# Photodiode.net
KiCad netlist of a schematic drawn in Altium Designer
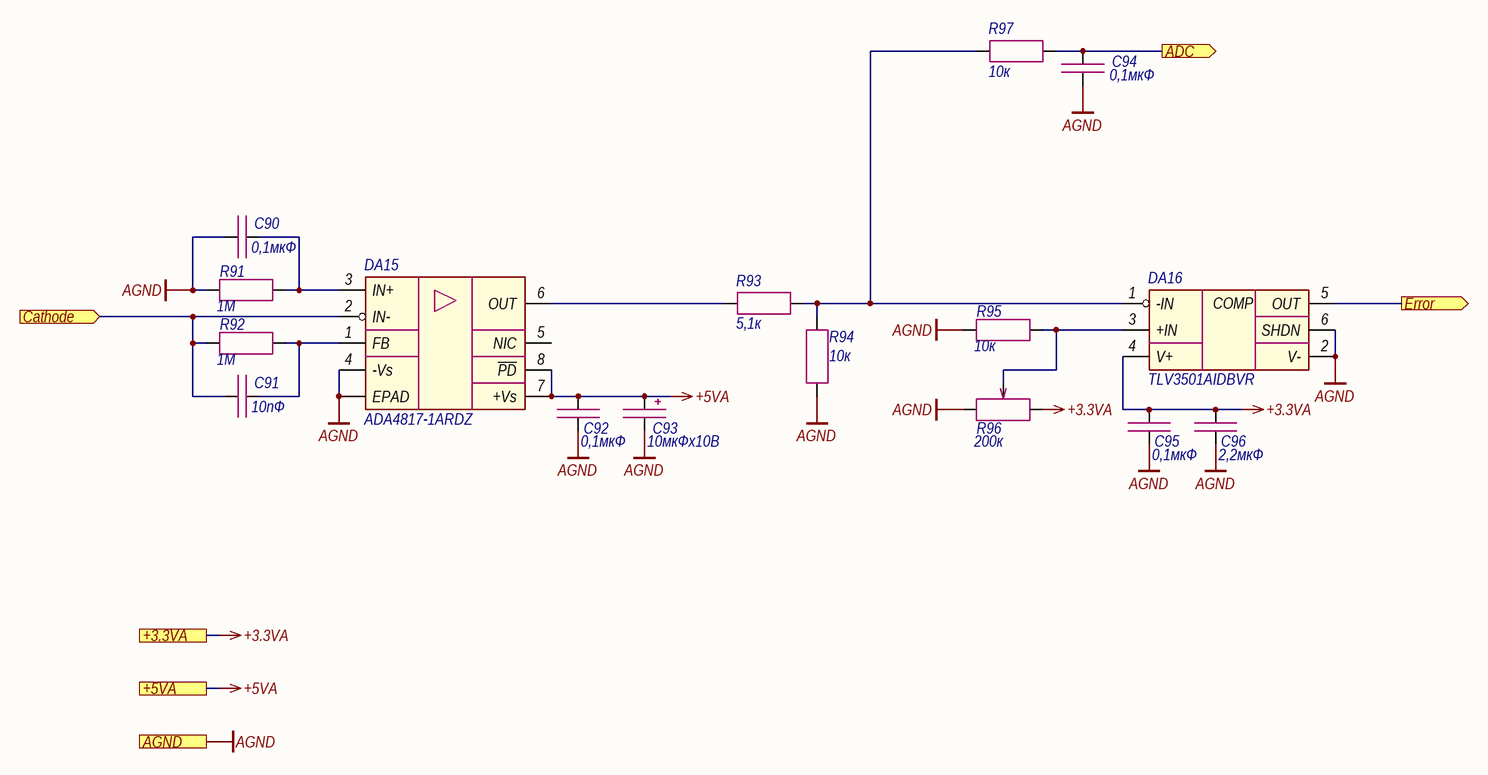
[diagram p0: Photodiode.SchDoc]

(export (version "E")
  (design (tool "Eeschema 10.0.6"))
  (components
    (comp (ref "C90")
      (value "0,1мкФ")
      (footprint "Pcb_library:CAP_0603")
      (fields (field (name "MANUFACTURER") "Murata"))
      (libsource (lib "Schem_library") (part "Capacitor"))
    )
    (comp (ref "C91")
      (value "10пФ")
      (footprint "Pcb_library:CAP_0603")
      (fields (field (name "MANUFACTURER") "Murata"))
      (libsource (lib "Schem_library") (part "Capacitor"))
    )
    (comp (ref "C92")
      (value "0,1мкФ")
      (footprint "Pcb_library:CAP_0603")
      (fields (field (name "MANUFACTURER") "Murata"))
      (libsource (lib "Schem_library") (part "Capacitor"))
    )
    (comp (ref "C93")
      (value "10мкФх10B")
      (footprint "Pcb_library:CAP_A")
      (libsource (lib "Schem_library") (part "Capacitor_Polar"))
    )
    (comp (ref "C94")
      (value "0,1мкФ")
      (footprint "Pcb_library:CAP_0603")
      (fields (field (name "MANUFACTURER") "Murata"))
      (libsource (lib "Schem_library") (part "Capacitor"))
    )
    (comp (ref "C95")
      (value "0,1мкФ")
      (footprint "Pcb_library:CAP_0603")
      (fields (field (name "MANUFACTURER") "Murata"))
      (libsource (lib "Schem_library") (part "Capacitor"))
    )
    (comp (ref "C96")
      (value "2,2мкФ")
      (footprint "Pcb_library:CAP_0603")
      (fields (field (name "MANUFACTURER") "Murata"))
      (libsource (lib "Schem_library") (part "Capacitor"))
    )
    (comp (ref "DA15")
      (value "ADA4817-1ARDZ")
      (footprint "Pcb_library:SOIC-8 EPAD")
      (fields (field (name "MANUFACTURER") "Analog Devices"))
      (libsource (lib "Schem_library") (part "ADA4817-1ARDZ"))
    )
    (comp (ref "DA16")
      (value "TLV3501AIDBVR")
      (footprint "Pcb_library:SOT-23-6")
      (fields (field (name "MANUFACTURER") "Texas Instruments"))
      (libsource (lib "Schem_library") (part "TLV3501"))
    )
    (comp (ref "R91")
      (value "1М")
      (footprint "Pcb_library:RES_0805")
      (fields (field (name "MANUFACTURER") "Yageo"))
      (libsource (lib "Schem_library") (part "Resistor"))
    )
    (comp (ref "R92")
      (value "1М")
      (footprint "Pcb_library:RES_0805")
      (fields (field (name "MANUFACTURER") "Yageo"))
      (libsource (lib "Schem_library") (part "Resistor"))
    )
    (comp (ref "R93")
      (value "5,1к")
      (footprint "Pcb_library:RES_0603")
      (fields (field (name "MANUFACTURER") "Yageo"))
      (libsource (lib "Schem_library") (part "Resistor"))
    )
    (comp (ref "R94")
      (value "10к")
      (footprint "Pcb_library:RES_0603")
      (fields (field (name "MANUFACTURER") "Yageo"))
      (libsource (lib "Schem_library") (part "Resistor"))
    )
    (comp (ref "R95")
      (value "10к")
      (footprint "Pcb_library:RES_0603")
      (fields (field (name "MANUFACTURER") "Yageo"))
      (libsource (lib "Schem_library") (part "Resistor"))
    )
    (comp (ref "R96")
      (value "200к")
      (footprint "Pcb_library:3224W")
      (fields (field (name "MANUFACTURER") "Bourns"))
      (libsource (lib "Schem_library") (part "Resistor_Variable"))
    )
    (comp (ref "R97")
      (value "10к")
      (footprint "Pcb_library:RES_0603")
      (fields (field (name "MANUFACTURER") "Yageo"))
      (libsource (lib "Schem_library") (part "Resistor"))
    )
  )
  (nets
    (net (code "1") (name "+3.3VA") (class "Default")
      (node (ref "C95") (pin "1") (pinfunction "1_1") (pintype "passive"))
      (node (ref "C96") (pin "1") (pinfunction "1_1") (pintype "passive"))
      (node (ref "DA16") (pin "4") (pinfunction "V+_4") (pintype "passive"))
      (node (ref "R96") (pin "3") (pintype "passive"))
    )
    (net (code "2") (name "+5VA") (class "Default")
      (node (ref "C92") (pin "1") (pinfunction "1_1") (pintype "passive"))
      (node (ref "C93") (pin "1") (pinfunction "1_1") (pintype "passive"))
      (node (ref "DA15") (pin "7") (pinfunction "+Vs_7") (pintype "passive"))
      (node (ref "DA15") (pin "8") (pinfunction "~{PD}_8") (pintype "passive"))
    )
    (net (code "3") (name "/ADC") (class "Default")
      (node (ref "C94") (pin "1") (pinfunction "1_1") (pintype "passive"))
      (node (ref "R97") (pin "2") (pinfunction "2_2") (pintype "passive"))
    )
    (net (code "4") (name "/Cathode") (class "Default")
      (node (ref "C91") (pin "2") (pinfunction "2_2") (pintype "passive"))
      (node (ref "DA15") (pin "2") (pinfunction "IN-_2") (pintype "passive"))
      (node (ref "R92") (pin "2") (pinfunction "2_2") (pintype "passive"))
    )
    (net (code "5") (name "/Error") (class "Default")
      (node (ref "DA16") (pin "5") (pinfunction "OUT_5") (pintype "passive"))
    )
    (net (code "6") (name "AGND") (class "Default")
      (node (ref "C90") (pin "1") (pinfunction "1_1") (pintype "passive"))
      (node (ref "C92") (pin "2") (pinfunction "2_2") (pintype "passive"))
      (node (ref "C93") (pin "2") (pinfunction "2_2") (pintype "passive"))
      (node (ref "C94") (pin "2") (pinfunction "2_2") (pintype "passive"))
      (node (ref "C95") (pin "2") (pinfunction "2_2") (pintype "passive"))
      (node (ref "C96") (pin "2") (pinfunction "2_2") (pintype "passive"))
      (node (ref "DA15") (pin "4") (pinfunction "-Vs_4") (pintype "passive"))
      (node (ref "DA15") (pin "EPAD") (pinfunction "EPAD_EPAD") (pintype "passive"))
      (node (ref "DA16") (pin "2") (pinfunction "V-_2") (pintype "passive"))
      (node (ref "DA16") (pin "6") (pinfunction "SHDN_6") (pintype "passive"))
      (node (ref "R91") (pin "2") (pinfunction "2_2") (pintype "passive"))
      (node (ref "R94") (pin "2") (pinfunction "2_2") (pintype "passive"))
      (node (ref "R95") (pin "1") (pinfunction "1_1") (pintype "passive"))
      (node (ref "R96") (pin "1") (pintype "passive"))
    )
    (net (code "7") (name "Net-(DA15-FB)") (class "Default")
      (node (ref "C91") (pin "1") (pinfunction "1_1") (pintype "passive"))
      (node (ref "DA15") (pin "1") (pinfunction "FB_1") (pintype "passive"))
      (node (ref "R92") (pin "1") (pinfunction "1_1") (pintype "passive"))
    )
    (net (code "8") (name "Net-(DA15-IN+)") (class "Default")
      (node (ref "C90") (pin "2") (pinfunction "2_2") (pintype "passive"))
      (node (ref "DA15") (pin "3") (pinfunction "IN+_3") (pintype "passive"))
      (node (ref "R91") (pin "1") (pinfunction "1_1") (pintype "passive"))
    )
    (net (code "9") (name "Net-(DA15-OUT)") (class "Default")
      (node (ref "DA15") (pin "6") (pinfunction "OUT_6") (pintype "passive"))
      (node (ref "R93") (pin "1") (pinfunction "1_1") (pintype "passive"))
    )
    (net (code "10") (name "Net-(DA16-+IN)") (class "Default")
      (node (ref "DA16") (pin "3") (pinfunction "+IN_3") (pintype "passive"))
      (node (ref "R95") (pin "2") (pinfunction "2_2") (pintype "passive"))
      (node (ref "R96") (pin "2") (pintype "passive"))
    )
    (net (code "11") (name "Net-(DA16--IN)") (class "Default")
      (node (ref "DA16") (pin "1") (pinfunction "-IN_1") (pintype "passive"))
      (node (ref "R93") (pin "2") (pinfunction "2_2") (pintype "passive"))
      (node (ref "R94") (pin "1") (pinfunction "1_1") (pintype "passive"))
      (node (ref "R97") (pin "1") (pinfunction "1_1") (pintype "passive"))
    )
    (net (code "12") (name "unconnected-(DA15-NIC-Pad5)") (class "Default")
      (node (ref "DA15") (pin "5") (pinfunction "NIC_5") (pintype "passive"))
    )
  )
)
